# bmi160_breakout.net
KiCad netlist of a schematic drawn in EAGLE
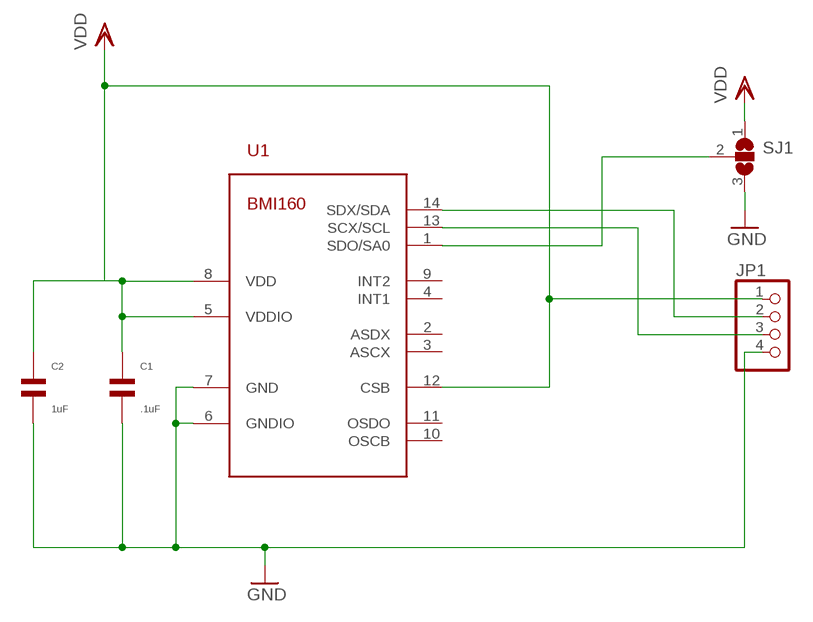
[diagram p0: schematic, sheet 1]

(export (version "E")
  (design (tool "Eeschema 10.0.6"))
  (components
    (comp (ref "C1")
      (value ".1uF")
      (footprint "eagle-import:C0603")
      (libsource (lib "eagle-import") (part "CAPACITOR_NP_0603"))
    )
    (comp (ref "C2")
      (value "1uF")
      (footprint "eagle-import:C0805")
      (libsource (lib "eagle-import") (part "CAPACITOR_NP_0805"))
    )
    (comp (ref "JP1")
      (value "PINHD-1X4")
      (footprint "eagle-import:1X04")
      (libsource (lib "eagle-import") (part "PINHD-1X4"))
    )
    (comp (ref "SJ1")
      (value "SJ2W")
      (footprint "eagle-import:SJ_2")
      (libsource (lib "eagle-import") (part "SJ2W"))
    )
    (comp (ref "U1")
      (value "BMI160LGA14")
      (footprint "eagle-import:LGA14")
      (fields (field (name "MPN") "BMI160"))
      (libsource (lib "eagle-import") (part "BMI160LGA14"))
    )
  )
  (nets
    (net (code "1") (name "GND") (class "Default")
      (node (ref "C1") (pin "P$2") (pinfunction "P$2_P$2") (pintype "passive"))
      (node (ref "C2") (pin "P$2") (pinfunction "P$2_P$2") (pintype "passive"))
      (node (ref "JP1") (pin "4") (pinfunction "4_4") (pintype "passive"))
      (node (ref "SJ1") (pin "3") (pinfunction "3_3") (pintype "passive"))
      (node (ref "U1") (pin "6") (pinfunction "GNDIO_6") (pintype "bidirectional"))
      (node (ref "U1") (pin "7") (pinfunction "GND_7") (pintype "bidirectional"))
    )
    (net (code "2") (name "Net-(U1-SCX{slash}SCL)") (class "Default")
      (node (ref "JP1") (pin "3") (pinfunction "3_3") (pintype "passive"))
      (node (ref "U1") (pin "13") (pinfunction "SCX/SCL_13") (pintype "bidirectional"))
    )
    (net (code "3") (name "Net-(U1-SDO{slash}SA0)") (class "Default")
      (node (ref "SJ1") (pin "2") (pinfunction "2_2") (pintype "passive"))
      (node (ref "U1") (pin "1") (pinfunction "SDO/SA0_1") (pintype "bidirectional"))
    )
    (net (code "4") (name "Net-(U1-SDX{slash}SDA)") (class "Default")
      (node (ref "JP1") (pin "2") (pinfunction "2_2") (pintype "passive"))
      (node (ref "U1") (pin "14") (pinfunction "SDX/SDA_14") (pintype "bidirectional"))
    )
    (net (code "5") (name "VDD") (class "Default")
      (node (ref "C1") (pin "P$1") (pinfunction "P$1_P$1") (pintype "passive"))
      (node (ref "C2") (pin "P$1") (pinfunction "P$1_P$1") (pintype "passive"))
      (node (ref "JP1") (pin "1") (pinfunction "1_1") (pintype "passive"))
      (node (ref "SJ1") (pin "1") (pinfunction "1_1") (pintype "passive"))
      (node (ref "U1") (pin "12") (pinfunction "CSB_12") (pintype "bidirectional"))
      (node (ref "U1") (pin "5") (pinfunction "VDDIO_5") (pintype "bidirectional"))
      (node (ref "U1") (pin "8") (pinfunction "VDD_8") (pintype "bidirectional"))
    )
    (net (code "6") (name "unconnected-(U1-ASCX-Pad3)") (class "Default")
      (node (ref "U1") (pin "3") (pinfunction "ASCX_3") (pintype "bidirectional"))
    )
    (net (code "7") (name "unconnected-(U1-ASDX-Pad2)") (class "Default")
      (node (ref "U1") (pin "2") (pinfunction "ASDX_2") (pintype "bidirectional"))
    )
    (net (code "8") (name "unconnected-(U1-INT1-Pad4)") (class "Default")
      (node (ref "U1") (pin "4") (pinfunction "INT1_4") (pintype "bidirectional"))
    )
    (net (code "9") (name "unconnected-(U1-INT2-Pad9)") (class "Default")
      (node (ref "U1") (pin "9") (pinfunction "INT2_9") (pintype "bidirectional"))
    )
    (net (code "10") (name "unconnected-(U1-OSCB-Pad10)") (class "Default")
      (node (ref "U1") (pin "10") (pinfunction "OSCB_10") (pintype "bidirectional"))
    )
    (net (code "11") (name "unconnected-(U1-OSDO-Pad11)") (class "Default")
      (node (ref "U1") (pin "11") (pinfunction "OSDO_11") (pintype "bidirectional"))
    )
  )
)
